# pure_battery.net
KiCad netlist of a schematic drawn in EAGLE
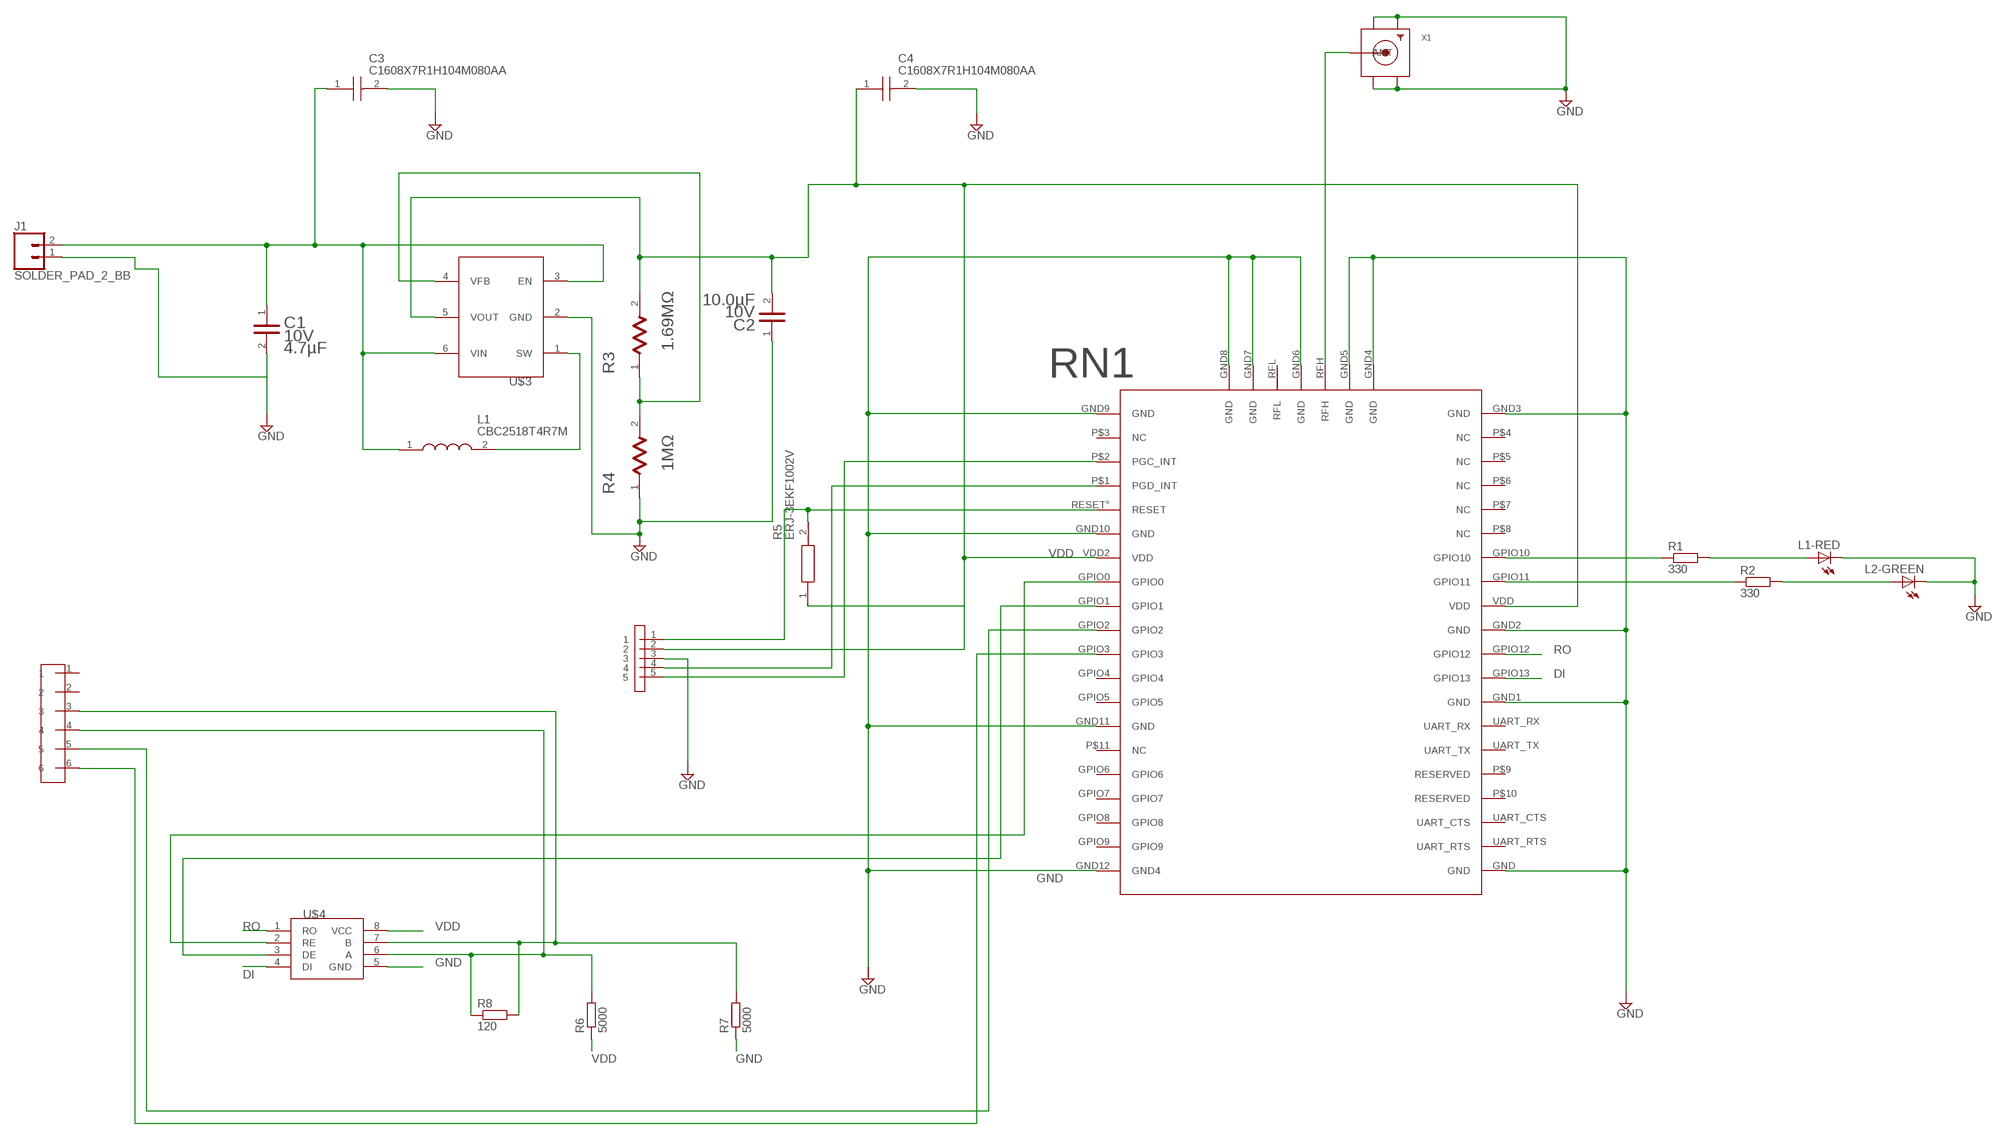
[diagram p0: schematic, sheet 1]

(export (version "E")
  (design (tool "Eeschema 10.0.6"))
  (components
    (comp (ref "C1")
      (value "KEMET_C0603C475K8PACTUKEMET_C0603C475K8PACTU_0_0")
      (footprint "eagle-import:KEMET_C0603C475K8PACTU_0")
      (fields
        (field (name "DIGIKEY_PART_NUMBER") "399-5503-1-ND")
        (field (name "MF") "Kemet")
        (field (name "MOUSER_PART_NUMBER") "80-C0603C475K8P")
      )
      (libsource (lib "eagle-import") (part "KEMET_C0603C475K8PACTUKEMET_C0603C475K8PACTU_0_0"))
    )
    (comp (ref "C2")
      (value "TDK_C1608X5R1A106M080ACTDK_C1608X5R1A106M080AC_0_0")
      (footprint "eagle-import:TDK_C1608X5R1A106M080AC_0")
      (fields
        (field (name "DIGIKEY_PART_NUMBER") "445-6853-1-ND")
        (field (name "MF") "TDK")
        (field (name "MOUSER_PART_NUMBER") "810-C1608X5R1A106M")
      )
      (libsource (lib "eagle-import") (part "TDK_C1608X5R1A106M080ACTDK_C1608X5R1A106M080AC_0_0"))
    )
    (comp (ref "C3")
      (value "C1608X7R1H104M080AA")
      (footprint "eagle-import:CAPC1608X80N")
      (fields (field (name "MOUSER_PART_NUMBER") "810-C1608X7R1H104M"))
      (libsource (lib "eagle-import") (part "C1608X7R1H104M080AA"))
    )
    (comp (ref "C4")
      (value "C1608X7R1H104M080AA")
      (footprint "eagle-import:CAPC1608X80N")
      (fields (field (name "MOUSER_PART_NUMBER") "810-C1608X7R1H104M"))
      (libsource (lib "eagle-import") (part "C1608X7R1H104M080AA"))
    )
    (comp (ref "J1")
      (value "SOLDER_PAD_2_BB")
      (footprint "eagle-import:SOLDER_PAD_2")
      (libsource (lib "eagle-import") (part "SOLDER_PAD_2_BB"))
    )
    (comp (ref "L1")
      (value "CBC2518T4R7M")
      (footprint "eagle-import:INDC2518X200N")
      (fields (field (name "MOUSER_PART_NUMBER") "963-CBC2518T4R7M"))
      (libsource (lib "eagle-import") (part "CBC2518T4R7M"))
    )
    (comp (ref "L1-RED")
      (value "LEDCHIP-LED0603")
      (footprint "eagle-import:CHIP-LED0603")
      (libsource (lib "eagle-import") (part "LEDCHIP-LED0603"))
    )
    (comp (ref "L2-GREEN")
      (value "LEDCHIP-LED0603")
      (footprint "eagle-import:CHIP-LED0603")
      (libsource (lib "eagle-import") (part "LEDCHIP-LED0603"))
    )
    (comp (ref "R1")
      (value "330")
      (footprint "eagle-import:R0603")
      (libsource (lib "eagle-import") (part "R-EU_R0603"))
    )
    (comp (ref "R2")
      (value "330")
      (footprint "eagle-import:R0603")
      (libsource (lib "eagle-import") (part "R-EU_R0603"))
    )
    (comp (ref "R3")
      (value "VISHAY_CRCW06031M69FKEAVISHAY_CRCW06031M69FKEA_0_1")
      (footprint "eagle-import:VISHAY_CRCW06031M69FKEA_1")
      (fields
        (field (name "APPROVED_ALTERNATE_PART_NUMBER") "541-1.00HHCT-ND")
        (field (name "DIGIKEY_PART_NUMBER") "541-1.69MHTR-ND")
        (field (name "MF") "Vishay")
      )
      (libsource (lib "eagle-import") (part "VISHAY_CRCW06031M69FKEAVISHAY_CRCW06031M69FKEA_0_1"))
    )
    (comp (ref "R4")
      (value "STACKPOLE_RMCF0603FT1M00STACKPOLE_RMCF0603FT1M00_0_1")
      (footprint "eagle-import:STACKPOLE_RMCF0603FT1M00_1")
      (fields
        (field (name "APPROVED_ALTERNATE_PART_NUMBER") "541-1.00HHCT-ND")
        (field (name "DIGIKEY_PART_NUMBER") "RMCF0603FT1M00-ND")
        (field (name "MF") "Stackpole")
      )
      (libsource (lib "eagle-import") (part "STACKPOLE_RMCF0603FT1M00STACKPOLE_RMCF0603FT1M00_0_1"))
    )
    (comp (ref "R5")
      (value "ERJ-3EKF1002V")
      (footprint "eagle-import:RESC1608X55N")
      (fields (field (name "MOUSER_PART_NUMBER") "667-ERJ-3EKF1002V"))
      (libsource (lib "eagle-import") (part "ERJ-3EKF1002V"))
    )
    (comp (ref "R6")
      (value "5000")
      (footprint "eagle-import:R0805")
      (libsource (lib "eagle-import") (part "R-EU_R0805"))
    )
    (comp (ref "R7")
      (value "5000")
      (footprint "eagle-import:R0805")
      (libsource (lib "eagle-import") (part "R-EU_R0805"))
    )
    (comp (ref "R8")
      (value "120")
      (footprint "eagle-import:R0805")
      (libsource (lib "eagle-import") (part "R-EU_R0805"))
    )
    (comp (ref "RN1")
      (value "NEW_RN2483")
      (footprint "eagle-import:NEW_RN2483")
      (libsource (lib "eagle-import") (part "NEW_RN2483"))
    )
    (comp (ref "U$1")
      (value "CONNECTOR62")
      (footprint "eagle-import:CONNECTOR6")
      (libsource (lib "eagle-import") (part "CONNECTOR62"))
    )
    (comp (ref "U$2")
      (value "ICSP52")
      (footprint "eagle-import:ICSP")
      (libsource (lib "eagle-import") (part "ICSP52"))
    )
    (comp (ref "U$3")
      (value "MCP16252")
      (footprint "eagle-import:MCP16252")
      (libsource (lib "eagle-import") (part "MCP16252"))
    )
    (comp (ref "U$4")
      (value "AMD3485E")
      (footprint "eagle-import:AMD3485E")
      (libsource (lib "eagle-import") (part "AMD3485E"))
    )
    (comp (ref "X1")
      (value "SMACONNECTOR_EDGE")
      (footprint "eagle-import:SMA_EDGELAUNCH")
      (libsource (lib "eagle-import") (part "SMACONNECTOR_EDGE"))
    )
  )
  (nets
    (net (code "1") (name "/DI") (class "Default")
      (node (ref "RN1") (pin "GPIO13") (pinfunction "GPIO13_GPIO13") (pintype "bidirectional"))
      (node (ref "U$4") (pin "4") (pinfunction "DI_4") (pintype "bidirectional"))
    )
    (net (code "2") (name "/RO") (class "Default")
      (node (ref "RN1") (pin "GPIO12") (pinfunction "GPIO12_GPIO12") (pintype "bidirectional"))
      (node (ref "U$4") (pin "1") (pinfunction "RO_1") (pintype "bidirectional"))
    )
    (net (code "3") (name "/VDD") (class "Default")
      (node (ref "C2") (pin "2") (pinfunction "2_2") (pintype "bidirectional"))
      (node (ref "C4") (pin "1") (pinfunction "1_1") (pintype "bidirectional"))
      (node (ref "R3") (pin "2") (pinfunction "2_2") (pintype "passive"))
      (node (ref "R5") (pin "1") (pinfunction "1_1") (pintype "bidirectional"))
      (node (ref "R6") (pin "1") (pinfunction "1_1") (pintype "passive"))
      (node (ref "RN1") (pin "VDD") (pinfunction "VDD_VDD") (pintype "bidirectional"))
      (node (ref "RN1") (pin "VDD2") (pinfunction "VDD_VDD2") (pintype "bidirectional"))
      (node (ref "U$2") (pin "2") (pinfunction "2_2") (pintype "bidirectional"))
      (node (ref "U$3") (pin "5") (pinfunction "VOUT_5") (pintype "bidirectional"))
      (node (ref "U$4") (pin "8") (pinfunction "VCC_8") (pintype "bidirectional"))
    )
    (net (code "4") (name "GND") (class "Default")
      (node (ref "C1") (pin "2") (pinfunction "2_2") (pintype "bidirectional"))
      (node (ref "C2") (pin "1") (pinfunction "1_1") (pintype "bidirectional"))
      (node (ref "C3") (pin "2") (pinfunction "2_2") (pintype "bidirectional"))
      (node (ref "C4") (pin "2") (pinfunction "2_2") (pintype "bidirectional"))
      (node (ref "J1") (pin "1") (pinfunction "1_1") (pintype "passive"))
      (node (ref "L1-RED") (pin "C") (pinfunction "C_C") (pintype "passive"))
      (node (ref "L2-GREEN") (pin "C") (pinfunction "C_C") (pintype "passive"))
      (node (ref "R4") (pin "1") (pinfunction "1_1") (pintype "passive"))
      (node (ref "R7") (pin "1") (pinfunction "1_1") (pintype "passive"))
      (node (ref "RN1") (pin "GND") (pinfunction "GND_GND") (pintype "bidirectional"))
      (node (ref "RN1") (pin "GND1") (pinfunction "GND_GND1") (pintype "bidirectional"))
      (node (ref "RN1") (pin "GND10") (pinfunction "GND_GND10") (pintype "bidirectional"))
      (node (ref "RN1") (pin "GND11") (pinfunction "GND_GND11") (pintype "bidirectional"))
      (node (ref "RN1") (pin "GND12") (pinfunction "GND4_GND12") (pintype "bidirectional"))
      (node (ref "RN1") (pin "GND2") (pinfunction "GND_GND2") (pintype "bidirectional"))
      (node (ref "RN1") (pin "GND3") (pinfunction "GND_GND3") (pintype "bidirectional"))
      (node (ref "RN1") (pin "GND4") (pinfunction "GND_GND4") (pintype "bidirectional"))
      (node (ref "RN1") (pin "GND5") (pinfunction "GND_GND5") (pintype "bidirectional"))
      (node (ref "RN1") (pin "GND6") (pinfunction "GND_GND6") (pintype "bidirectional"))
      (node (ref "RN1") (pin "GND7") (pinfunction "GND_GND7") (pintype "bidirectional"))
      (node (ref "RN1") (pin "GND8") (pinfunction "GND_GND8") (pintype "bidirectional"))
      (node (ref "RN1") (pin "GND9") (pinfunction "GND_GND9") (pintype "bidirectional"))
      (node (ref "U$2") (pin "3") (pinfunction "3_3") (pintype "bidirectional"))
      (node (ref "U$3") (pin "2") (pinfunction "GND_2") (pintype "bidirectional"))
      (node (ref "U$4") (pin "5") (pinfunction "GND_5") (pintype "bidirectional"))
      (node (ref "X1") (pin "GND@1") (pinfunction "GND4_GND@1") (pintype "power_in"))
      (node (ref "X1") (pin "GND@2") (pinfunction "GND3_GND@2") (pintype "power_in"))
      (node (ref "X1") (pin "GND@3") (pinfunction "GND2_GND@3") (pintype "power_in"))
      (node (ref "X1") (pin "GND@4") (pinfunction "GND1_GND@4") (pintype "power_in"))
    )
    (net (code "5") (name "Net-(L1-RED-PadA)") (class "Default")
      (node (ref "L1-RED") (pin "A") (pinfunction "A_A") (pintype "passive"))
      (node (ref "R1") (pin "2") (pinfunction "2_2") (pintype "passive"))
    )
    (net (code "6") (name "Net-(L2-GREEN-PadA)") (class "Default")
      (node (ref "L2-GREEN") (pin "A") (pinfunction "A_A") (pintype "passive"))
      (node (ref "R2") (pin "2") (pinfunction "2_2") (pintype "passive"))
    )
    (net (code "7") (name "Net-(R1-Pad1)") (class "Default")
      (node (ref "R1") (pin "1") (pinfunction "1_1") (pintype "passive"))
      (node (ref "RN1") (pin "GPIO10") (pinfunction "GPIO10_GPIO10") (pintype "bidirectional"))
    )
    (net (code "8") (name "Net-(R2-Pad1)") (class "Default")
      (node (ref "R2") (pin "1") (pinfunction "1_1") (pintype "passive"))
      (node (ref "RN1") (pin "GPIO11") (pinfunction "GPIO11_GPIO11") (pintype "bidirectional"))
    )
    (net (code "9") (name "Net-(RN1-PGC_INT)") (class "Default")
      (node (ref "RN1") (pin "P$2") (pinfunction "PGC_INT_P$2") (pintype "bidirectional"))
      (node (ref "U$2") (pin "5") (pinfunction "5_5") (pintype "bidirectional"))
    )
    (net (code "10") (name "Net-(RN1-PGD_INT)") (class "Default")
      (node (ref "RN1") (pin "P$1") (pinfunction "PGD_INT_P$1") (pintype "bidirectional"))
      (node (ref "U$2") (pin "4") (pinfunction "4_4") (pintype "bidirectional"))
    )
    (net (code "11") (name "Net-(RN1-PadGPIO2)") (class "Default")
      (node (ref "RN1") (pin "GPIO2") (pinfunction "GPIO2_GPIO2") (pintype "bidirectional"))
      (node (ref "U$1") (pin "5") (pinfunction "5_5") (pintype "bidirectional"))
    )
    (net (code "12") (name "Net-(RN1-PadGPIO3)") (class "Default")
      (node (ref "RN1") (pin "GPIO3") (pinfunction "GPIO3_GPIO3") (pintype "bidirectional"))
      (node (ref "U$1") (pin "6") (pinfunction "6_6") (pintype "bidirectional"))
    )
    (net (code "13") (name "Net-(RN1-RESET)") (class "Default")
      (node (ref "R5") (pin "2") (pinfunction "2_2") (pintype "bidirectional"))
      (node (ref "RN1") (pin "RESET°") (pinfunction "RESET_RESET°") (pintype "bidirectional"))
      (node (ref "U$2") (pin "1") (pinfunction "1_1") (pintype "bidirectional"))
    )
    (net (code "14") (name "Net-(U$3-EN)") (class "Default")
      (node (ref "C1") (pin "1") (pinfunction "1_1") (pintype "bidirectional"))
      (node (ref "C3") (pin "1") (pinfunction "1_1") (pintype "bidirectional"))
      (node (ref "J1") (pin "2") (pinfunction "2_2") (pintype "passive"))
      (node (ref "L1") (pin "1") (pinfunction "1_1") (pintype "bidirectional"))
      (node (ref "U$3") (pin "3") (pinfunction "EN_3") (pintype "bidirectional"))
      (node (ref "U$3") (pin "6") (pinfunction "VIN_6") (pintype "bidirectional"))
    )
    (net (code "15") (name "Net-(U$3-SW)") (class "Default")
      (node (ref "L1") (pin "2") (pinfunction "2_2") (pintype "bidirectional"))
      (node (ref "U$3") (pin "1") (pinfunction "SW_1") (pintype "bidirectional"))
    )
    (net (code "16") (name "Net-(U$3-VFB)") (class "Default")
      (node (ref "R3") (pin "1") (pinfunction "1_1") (pintype "passive"))
      (node (ref "R4") (pin "2") (pinfunction "2_2") (pintype "passive"))
      (node (ref "U$3") (pin "4") (pinfunction "VFB_4") (pintype "bidirectional"))
    )
    (net (code "17") (name "Net-(U$4-A)") (class "Default")
      (node (ref "R6") (pin "2") (pinfunction "2_2") (pintype "passive"))
      (node (ref "R8") (pin "1") (pinfunction "1_1") (pintype "passive"))
      (node (ref "U$1") (pin "4") (pinfunction "4_4") (pintype "bidirectional"))
      (node (ref "U$4") (pin "6") (pinfunction "A_6") (pintype "bidirectional"))
    )
    (net (code "18") (name "Net-(U$4-B)") (class "Default")
      (node (ref "R7") (pin "2") (pinfunction "2_2") (pintype "passive"))
      (node (ref "R8") (pin "2") (pinfunction "2_2") (pintype "passive"))
      (node (ref "U$1") (pin "3") (pinfunction "3_3") (pintype "bidirectional"))
      (node (ref "U$4") (pin "7") (pinfunction "B_7") (pintype "bidirectional"))
    )
    (net (code "19") (name "Net-(U$4-DE)") (class "Default")
      (node (ref "RN1") (pin "GPIO1") (pinfunction "GPIO1_GPIO1") (pintype "bidirectional"))
      (node (ref "U$4") (pin "3") (pinfunction "DE_3") (pintype "bidirectional"))
    )
    (net (code "20") (name "Net-(U$4-RE)") (class "Default")
      (node (ref "RN1") (pin "GPIO0") (pinfunction "GPIO0_GPIO0") (pintype "bidirectional"))
      (node (ref "U$4") (pin "2") (pinfunction "RE_2") (pintype "bidirectional"))
    )
    (net (code "21") (name "Net-(X1-ANT)") (class "Default")
      (node (ref "RN1") (pin "RFH") (pinfunction "RFH_RFH") (pintype "bidirectional"))
      (node (ref "X1") (pin "P") (pinfunction "ANT_P") (pintype "bidirectional"))
    )
    (net (code "22") (name "unconnected-(RN1-NC-PadP$3)") (class "Default")
      (node (ref "RN1") (pin "P$3") (pinfunction "NC_P$3") (pintype "bidirectional"))
    )
    (net (code "23") (name "unconnected-(RN1-NC-PadP$4)") (class "Default")
      (node (ref "RN1") (pin "P$4") (pinfunction "NC_P$4") (pintype "bidirectional"))
    )
    (net (code "24") (name "unconnected-(RN1-NC-PadP$5)") (class "Default")
      (node (ref "RN1") (pin "P$5") (pinfunction "NC_P$5") (pintype "bidirectional"))
    )
    (net (code "25") (name "unconnected-(RN1-NC-PadP$6)") (class "Default")
      (node (ref "RN1") (pin "P$6") (pinfunction "NC_P$6") (pintype "bidirectional"))
    )
    (net (code "26") (name "unconnected-(RN1-NC-PadP$7)") (class "Default")
      (node (ref "RN1") (pin "P$7") (pinfunction "NC_P$7") (pintype "bidirectional"))
    )
    (net (code "27") (name "unconnected-(RN1-NC-PadP$8)") (class "Default")
      (node (ref "RN1") (pin "P$8") (pinfunction "NC_P$8") (pintype "bidirectional"))
    )
    (net (code "28") (name "unconnected-(RN1-NC-PadP$11)") (class "Default")
      (node (ref "RN1") (pin "P$11") (pinfunction "NC_P$11") (pintype "bidirectional"))
    )
    (net (code "29") (name "unconnected-(RN1-PadGPIO4)") (class "Default")
      (node (ref "RN1") (pin "GPIO4") (pinfunction "GPIO4_GPIO4") (pintype "bidirectional"))
    )
    (net (code "30") (name "unconnected-(RN1-PadGPIO5)") (class "Default")
      (node (ref "RN1") (pin "GPIO5") (pinfunction "GPIO5_GPIO5") (pintype "bidirectional"))
    )
    (net (code "31") (name "unconnected-(RN1-PadGPIO6)") (class "Default")
      (node (ref "RN1") (pin "GPIO6") (pinfunction "GPIO6_GPIO6") (pintype "bidirectional"))
    )
    (net (code "32") (name "unconnected-(RN1-PadGPIO7)") (class "Default")
      (node (ref "RN1") (pin "GPIO7") (pinfunction "GPIO7_GPIO7") (pintype "bidirectional"))
    )
    (net (code "33") (name "unconnected-(RN1-PadGPIO8)") (class "Default")
      (node (ref "RN1") (pin "GPIO8") (pinfunction "GPIO8_GPIO8") (pintype "bidirectional"))
    )
    (net (code "34") (name "unconnected-(RN1-PadGPIO9)") (class "Default")
      (node (ref "RN1") (pin "GPIO9") (pinfunction "GPIO9_GPIO9") (pintype "bidirectional"))
    )
    (net (code "35") (name "unconnected-(RN1-PadRFL)") (class "Default")
      (node (ref "RN1") (pin "RFL") (pinfunction "RFL_RFL") (pintype "bidirectional"))
    )
    (net (code "36") (name "unconnected-(RN1-PadUART_CTS)") (class "Default")
      (node (ref "RN1") (pin "UART_CTS") (pinfunction "UART_CTS_UART_CTS") (pintype "bidirectional"))
    )
    (net (code "37") (name "unconnected-(RN1-PadUART_RTS)") (class "Default")
      (node (ref "RN1") (pin "UART_RTS") (pinfunction "UART_RTS_UART_RTS") (pintype "bidirectional"))
    )
    (net (code "38") (name "unconnected-(RN1-PadUART_RX)") (class "Default")
      (node (ref "RN1") (pin "UART_RX") (pinfunction "UART_RX_UART_RX") (pintype "bidirectional"))
    )
    (net (code "39") (name "unconnected-(RN1-PadUART_TX)") (class "Default")
      (node (ref "RN1") (pin "UART_TX") (pinfunction "UART_TX_UART_TX") (pintype "bidirectional"))
    )
    (net (code "40") (name "unconnected-(RN1-RESERVED-PadP$9)") (class "Default")
      (node (ref "RN1") (pin "P$9") (pinfunction "RESERVED_P$9") (pintype "bidirectional"))
    )
    (net (code "41") (name "unconnected-(RN1-RESERVED-PadP$10)") (class "Default")
      (node (ref "RN1") (pin "P$10") (pinfunction "RESERVED_P$10") (pintype "bidirectional"))
    )
    (net (code "42") (name "unconnected-(U$1-Pad1)") (class "Default")
      (node (ref "U$1") (pin "1") (pinfunction "1_1") (pintype "bidirectional"))
    )
    (net (code "43") (name "unconnected-(U$1-Pad2)") (class "Default")
      (node (ref "U$1") (pin "2") (pinfunction "2_2") (pintype "bidirectional"))
    )
  )
)
